# Power_Supplies.net
KiCad netlist of a schematic drawn in Altium Designer
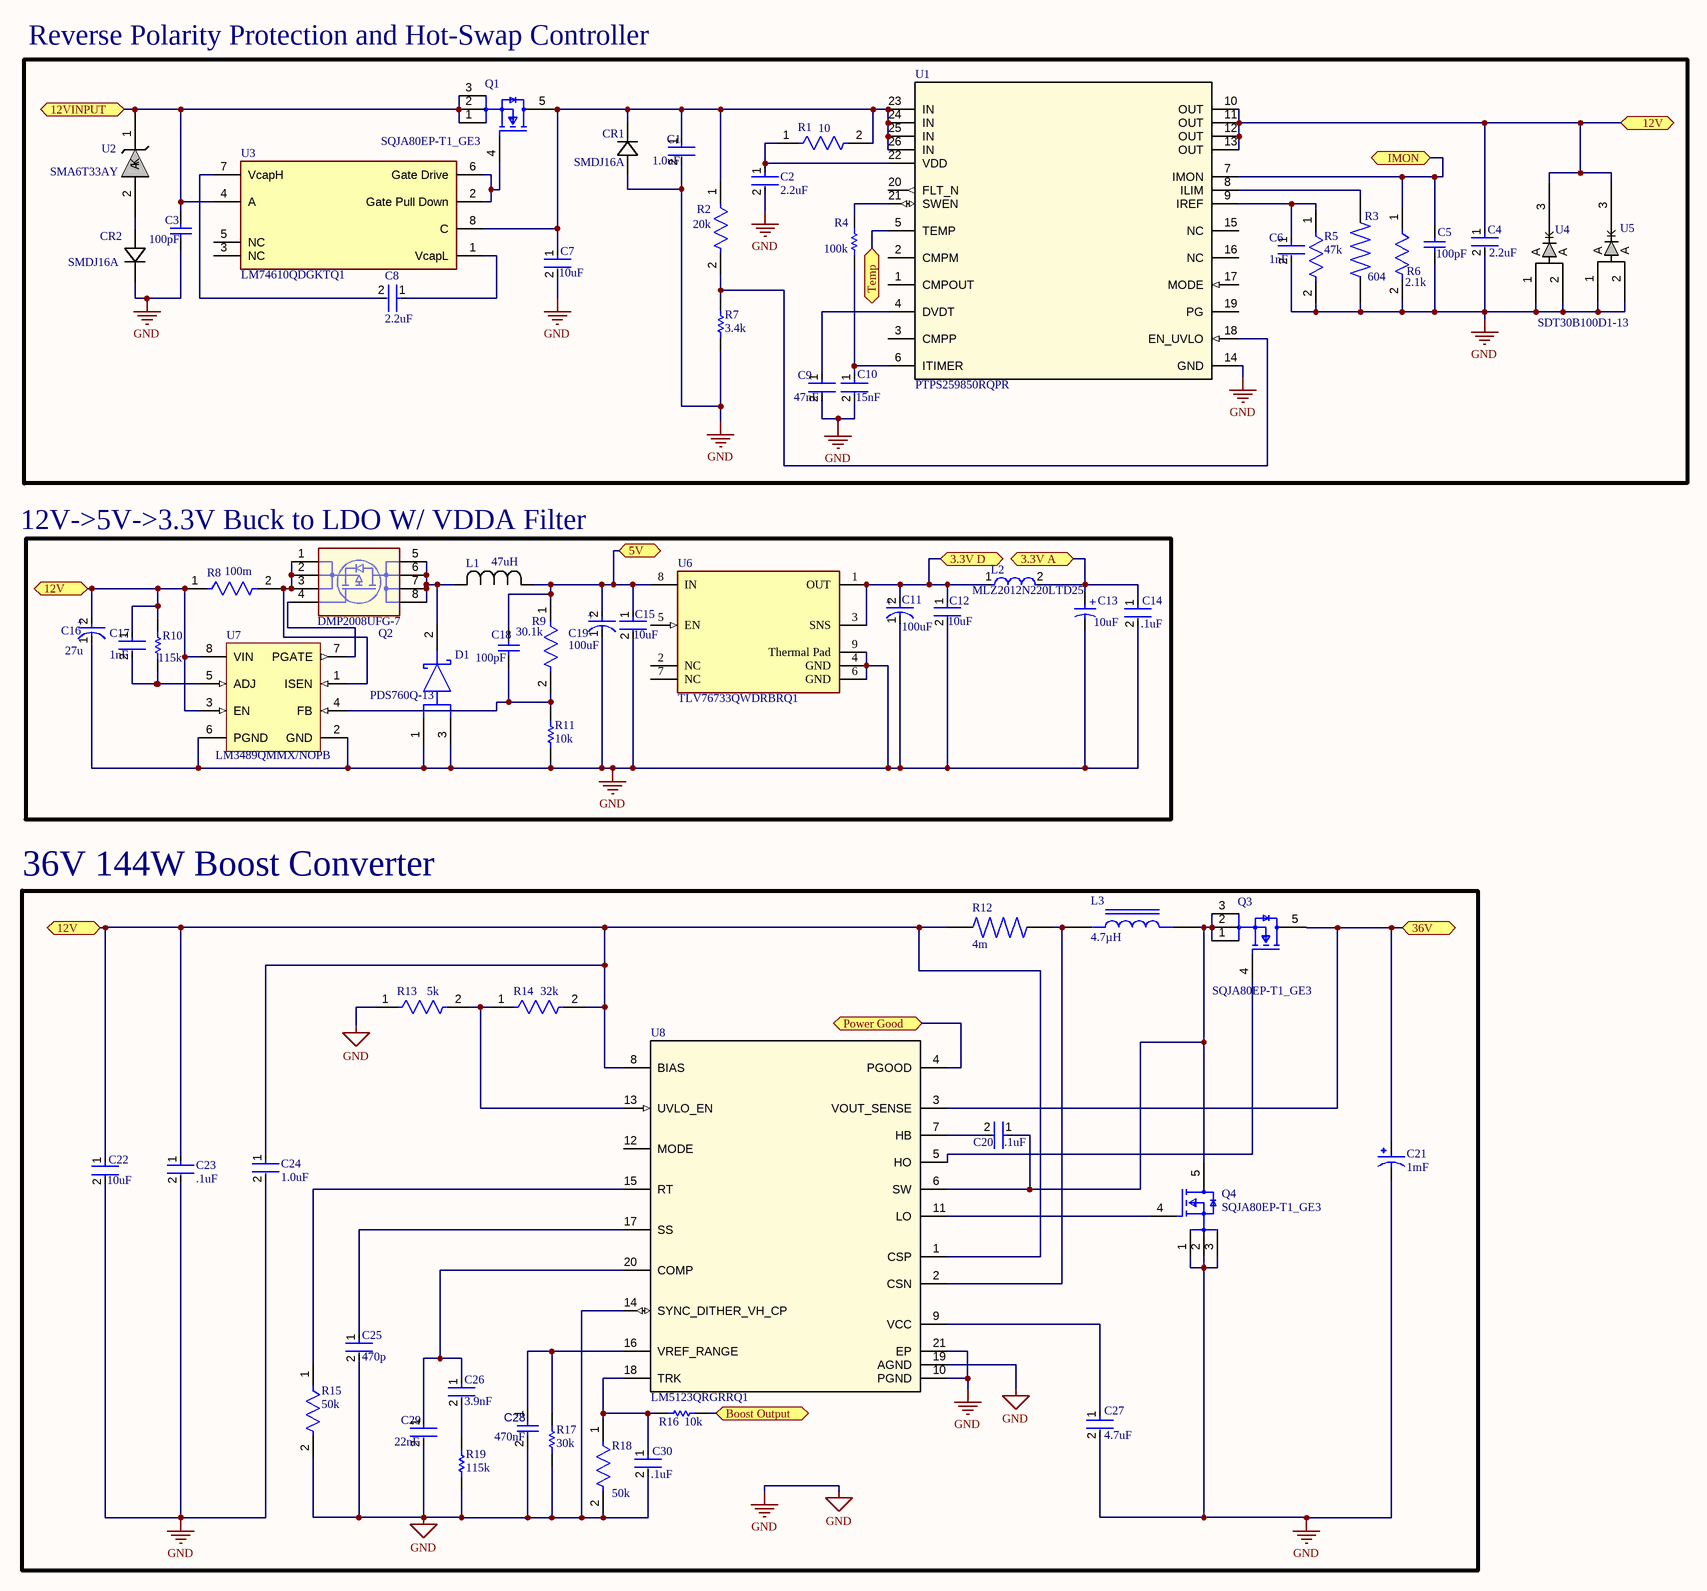
[diagram p0: Power_Supplies.SchDoc]

(export (version "E")
  (design (tool "Eeschema 10.0.6"))
  (components
    (comp (ref "C1")
      (value "1.0uF")
      (footprint "FP-GRM155-0_1-MFG")
      (description "Chip Multilayer Ceramic Capacitors for General Purpose, 0402, 1.0uF, X5R, 15%, 10%, 50V")
      (libsource (lib "Altium Content Vault") (part "11868f565c42a9108669ba33697ecf6"))
    )
    (comp (ref "C2")
      (value "2.2uF")
      (footprint "FP-GRM155-0_2-IPC_B")
      (description "Chip Multilayer Ceramic Capacitors for General Purpose, 0402, 2.2uF, X5R, 15%, 10%, 16V")
      (fields (field (name "TOLERANCE") "10%"))
      (libsource (lib "Altium Content Vault") (part "b4654b650e69147ec39a6b967a45e02"))
    )
    (comp (ref "C3")
      (value "100pF")
      (footprint "CAPC1005X55X25ML05T05")
      (description "Multilayer Ceramic Capacitor, 100 pF, 25 V, ± 10%, X7R, 0402 [1005 Metric]")
      (fields (field (name "PART NUMBER") "VJ0402Y101KXXPW1BC") (field (name "MANUFACTURER") "Vitramon"))
      (libsource (lib "Altium Content Vault") (part "CAP"))
    )
    (comp (ref "C4")
      (value "2.2uF")
      (footprint "FP-GRM155-0_2-IPC_B")
      (description "Chip Multilayer Ceramic Capacitors for General Purpose, 0402, 2.2uF, X5R, 15%, 10%, 16V")
      (fields (field (name "TOLERANCE") "10%"))
      (libsource (lib "Altium Content Vault") (part "b4654b650e69147ec39a6b967a45e02"))
    )
    (comp (ref "C5")
      (value "100pF")
      (footprint "CAPC1005X55X25ML05T05")
      (description "Multilayer Ceramic Capacitor, 100 pF, 25 V, ± 10%, X7R, 0402 [1005 Metric]")
      (fields (field (name "PART NUMBER") "VJ0402Y101KXXPW1BC") (field (name "MANUFACTURER") "Vitramon"))
      (libsource (lib "Altium Content Vault") (part "CAP"))
    )
    (comp (ref "C6")
      (value "1nF")
      (footprint "FP-C1005-050-0_05-IPC_B")
      (description "Multilayer Ceramic Capacitors 1nF ±5% 100V C0G SMD 0402")
      (fields (field (name "TOLERANCE") "5%"))
      (libsource (lib "Altium Content Vault") (part "b4654b650e69147ec39a6b967a45e02"))
    )
    (comp (ref "C7")
      (value "10uF")
      (footprint "FP-CL21-IPC_A")
      (description "CL21 Series 0805 10uF 25V ±10% Tolerance X5R Multilayer Ceramic Chip Capacitor")
      (fields (field (name "TOLERANCE") "10%"))
      (libsource (lib "Altium Content Vault") (part "b4654b650e69147ec39a6b967a45e02"))
    )
    (comp (ref "C8")
      (value "2.2uF")
      (footprint "FP-GRM155-0_2-IPC_B")
      (description "Chip Multilayer Ceramic Capacitors for General Purpose, 0402, 2.2uF, X5R, 15%, 10%, 16V")
      (fields (field (name "TOLERANCE") "10%"))
      (libsource (lib "Altium Content Vault") (part "b4654b650e69147ec39a6b967a45e02"))
    )
    (comp (ref "C9")
      (value "47nF")
      (footprint "FP-C1005-050-0_05-IPC_B")
      (description "Multilayer Ceramic Capacitors 47nF ±10% 35V X7R SMD 0402")
      (fields (field (name "TOLERANCE") "10%"))
      (libsource (lib "Altium Content Vault") (part "b4654b650e69147ec39a6b967a45e02"))
    )
    (comp (ref "C10")
      (value "15nF")
      (footprint "FP-GRT155-0_05-IPC_A")
      (description "Multi-Layer Ceramic Capacitor 15nF 50V X7R ±10% 0402 Paper T/R")
      (libsource (lib "Altium Content Vault") (part "02cd4be3c70576c341d710602a673aa"))
    )
    (comp (ref "C11")
      (value "100uF")
      (footprint "FP-FKF-MFG")
      (description "Radial Can - SMD ALUMINUM ELECTROLYTIC CAPACITOR FK 50V 100muF ±20% 0.315Dia 8.00mm")
      (fields (field (name "VOLTAGE") "50V") (field (name "TOLERANCE") "20%"))
      (libsource (lib "Altium Content Vault") (part "a00bbbee19879c290e62620ae7e47b1"))
    )
    (comp (ref "C12")
      (value "10uF")
      (footprint "FP-CL21-IPC_A")
      (description "CL21 Series 0805 10uF 25V ±10% Tolerance X5R Multilayer Ceramic Chip Capacitor")
      (fields (field (name "TOLERANCE") "10%"))
      (libsource (lib "Altium Content Vault") (part "b4654b650e69147ec39a6b967a45e02"))
    )
    (comp (ref "C13")
      (value "10uF")
      (footprint "WCAP-ASLI_D4H5.5")
      (description "865080340001 WCAP-ASLI Aluminum Electrolytic Capacitors")
      (fields (field (name "TOLERANCE") "20%"))
      (libsource (lib "Altium Content Vault") (part "Capacitor_Polarized"))
    )
    (comp (ref "C14")
      (value ".1uF")
      (footprint "FP-GRM155-0_05-MFG")
      (description "Chip Multilayer Ceramic Capacitors for General Purpose, 0402, 0.10uF, B, 10%, 10%, 50V")
      (fields (field (name "TOLERANCE") "10%"))
      (libsource (lib "Altium Content Vault") (part "02cd4be3c70576c341d710602a673aa"))
    )
    (comp (ref "C15")
      (value "10uF")
      (footprint "FP-CL21-IPC_A")
      (description "CL21 Series 0805 10uF 25V ±10% Tolerance X5R Multilayer Ceramic Chip Capacitor")
      (fields (field (name "TOLERANCE") "10%"))
      (libsource (lib "Altium Content Vault") (part "b4654b650e69147ec39a6b967a45e02"))
    )
    (comp (ref "C16")
      (value "27u")
      (footprint "FP-OS-CON-SMT-C6-MFG")
      (description "Conductive Polymer Aluminum Solid Capacitors (OS-CON) 27uF ±20% 20V")
      (fields (field (name "VOLTAGE") "20V") (field (name "TOLERANCE") "20%"))
      (libsource (lib "Altium Content Vault") (part "a00bbbee19879c290e62620ae7e47b1"))
    )
    (comp (ref "C17")
      (value "1nF")
      (footprint "FP-C1005-050-0_05-IPC_B")
      (description "Multilayer Ceramic Capacitors 1nF ±5% 100V C0G SMD 0402")
      (fields (field (name "TOLERANCE") "5%"))
      (libsource (lib "Altium Content Vault") (part "b4654b650e69147ec39a6b967a45e02"))
    )
    (comp (ref "C18")
      (value "100pF")
      (footprint "CAPC1005X55X25ML05T05")
      (fields (field (name "PART NUMBER") "VJ0402Y101KXXPW1BC") (field (name "MANUFACTURER") "Vitramon"))
      (libsource (lib "Altium Content Vault") (part "CAP"))
    )
    (comp (ref "C19")
      (value "100uF")
      (footprint "FP-FKF-MFG")
      (description "Radial Can - SMD ALUMINUM ELECTROLYTIC CAPACITOR FK 50V 100muF ±20% 0.315Dia 8.00mm")
      (fields (field (name "VOLTAGE") "50V") (field (name "TOLERANCE") "20%"))
      (libsource (lib "Altium Content Vault") (part "a00bbbee19879c290e62620ae7e47b1"))
    )
    (comp (ref "C20")
      (value ".1uF")
      (footprint "FP-GRM155-0_05-MFG")
      (description "Chip Multilayer Ceramic Capacitors for General Purpose, 0402, 0.10uF, B, 10%, 10%, 50V")
      (fields (field (name "TOLERANCE") "10%"))
      (libsource (lib "Altium Content Vault") (part "02cd4be3c70576c341d710602a673aa"))
    )
    (comp (ref "C21")
      (value "1mF")
      (footprint "CAP_EEEFK1H102AV")
      (description "1000ÂµF 50V Aluminum Electrolytic Capacitors Radial, Can - SMD 73mOhm @ 100kHz 5000 Hrs @ 105Â°C")
      (fields (field (name "MF") "Panasonic") (field (name "MP") "EEE-FK1H102AV"))
      (libsource (lib "Americas - California State Polytechnic University, Pomona - Bronco Motorsports") (part "EEEFK1H102AV"))
    )
    (comp (ref "C22")
      (value "10uF")
      (footprint "FP-CL21-IPC_A")
      (description "CL21 Series 0805 10uF 25V ±10% Tolerance X5R Multilayer Ceramic Chip Capacitor")
      (fields (field (name "TOLERANCE") "10%"))
      (libsource (lib "Altium Content Vault") (part "b4654b650e69147ec39a6b967a45e02"))
    )
    (comp (ref "C23")
      (value ".1uF")
      (footprint "FP-GRM155-0_05-MFG")
      (description "Chip Multilayer Ceramic Capacitors for General Purpose, 0402, 0.10uF, B, 10%, 10%, 50V")
      (fields (field (name "TOLERANCE") "10%"))
      (libsource (lib "Altium Content Vault") (part "02cd4be3c70576c341d710602a673aa"))
    )
    (comp (ref "C24")
      (value "1.0uF")
      (footprint "FP-GRM155-0_1-MFG")
      (description "Chip Multilayer Ceramic Capacitors for General Purpose, 0402, 1.0uF, X5R, 15%, 10%, 50V")
      (libsource (lib "Altium Content Vault") (part "11868f565c42a9108669ba33697ecf6"))
    )
    (comp (ref "C25")
      (value "470p")
      (footprint "FP-GCM155-0_1-IPC_A")
      (description "Ceramic Capacitor for Automotive 470nF ±20% 10VDC X7S 0402 Paper T/R")
      (libsource (lib "Altium Content Vault") (part "11868f565c42a9108669ba33697ecf6"))
    )
    (comp (ref "C26")
      (value "3.9nF")
      (footprint "FP-CC0402-MFG")
      (description "CAP CER 3900PF 50V X7R 0402")
      (fields
        (field (name "OCTOPART") "https://octopart.com/cc0402krx7r9bb392-yageo-9291741")
        (field (name "TOLERANCE") "0.1")
      )
      (libsource (lib "Altium Content Vault") (part "11868f565c42a9108669ba33697ecf6"))
    )
    (comp (ref "C27")
      (value "4.7uF")
      (footprint "FP-CL829-IPC_C")
      (description "Cap Ceramic 4.7uF 16V X5R ±20% SMD 0402 +85°C Paper T/R")
      (fields (field (name "TOLERANCE") "20%"))
      (libsource (lib "Altium Content Vault") (part "b4654b650e69147ec39a6b967a45e02"))
    )
    (comp (ref "C28")
      (value "470nF")
      (footprint "CAPC0402(1005)60_L")
      (description "Chip Capacitor, 470nF +/-40%, 10V, 0402, Thickness 0.6 mm")
      (fields (field (name "TOLERANCE") "20%") (field (name "Comment") "Capacitor 470nF +/-40% 10V 0402"))
      (libsource (lib "Americas - California State Polytechnic University, Pomona - Bronco Motorsports") (part "CAP-NP-2"))
    )
    (comp (ref "C29")
      (value "22nF")
      (footprint "FP-0402-L_1_0_0_05-W_0_5-IPC_B")
      (description "Multilayer Ceramic Capacitor 0.022uF 16V 10% 0402 Paper T/R")
      (libsource (lib "Altium Content Vault") (part "b4654b650e69147ec39a6b967a45e02"))
    )
    (comp (ref "C30")
      (value ".1uF")
      (footprint "FP-GRM155-0_05-MFG")
      (description "Chip Multilayer Ceramic Capacitors for General Purpose, 0402, 0.10uF, B, 10%, 10%, 50V")
      (fields (field (name "TOLERANCE") "10%"))
      (libsource (lib "Altium Content Vault") (part "02cd4be3c70576c341d710602a673aa"))
    )
    (comp (ref "CR1")
      (value "SMDJ16A")
      (footprint "SMDJSeries_LTF")
      (description "Description")
      (fields (field (name "COPYRIGHT") "Copyright (C) 2025 Ultra Librarian. All rights reserved."))
      (libsource (lib "Americas - California State Polytechnic University, Pomona - Bronco Motorsports") (part "SMDJ16A"))
    )
    (comp (ref "CR2")
      (value "SMDJ16A")
      (footprint "SMDJSeries_LTF")
      (description "Description")
      (fields (field (name "COPYRIGHT") "Copyright (C) 2025 Ultra Librarian. All rights reserved."))
      (libsource (lib "Americas - California State Polytechnic University, Pomona - Bronco Motorsports") (part "SMDJ16A"))
    )
    (comp (ref "D1")
      (value "PDS760Q-13")
      (footprint "FP-PowerDI5-MFG")
      (description "DIODE SCHOTTKY 60V 7A POWERDI5")
      (libsource (lib "Altium Content Vault") (part "72f53422dd85bf15edf9c11c54f6d52"))
    )
    (comp (ref "L1")
      (value "47uH")
      (footprint "IND_PA4343PM4343_FP2_PUL")
      (description "Description")
      (fields
        (field (name "MANUFACTURER_PART_NUMBER") "PM4343.473NLT")
        (field (name "COPYRIGHT") "Copyright (C) 2025 Ultra Librarian. All rights reserved.")
      )
      (libsource (lib "Americas - California State Polytechnic University, Pomona - Bronco Motorsports") (part "PM4343.473NLT"))
    )
    (comp (ref "L2")
      (value "MLZ2012N220LTD25")
      (footprint "FP-MLZ2012-1_25-IPC_A")
      (description "Shielded Multilayer Inductor 22uH ±20% 300mA 871mΩ AEC-Q200 SMD 0805")
      (fields (field (name "TOLERANCE") "20%"))
      (libsource (lib "Altium Content Vault") (part "725321dda6339637d4d059423bc1c3c"))
    )
    (comp (ref "L3")
      (value "4.7µH")
      (footprint "IND_PQ2614BLA-4R7K")
      (fields (field (name "MP") "PQ2614BLA-4R7K") (field (name "MF") "{'manufacturer': u'Bourns Inc.'}"))
      (libsource (lib "Americas - California State Polytechnic University, Pomona - Bronco Motorsports") (part "PQ2614BLA-4R7K"))
    )
    (comp (ref "Q1")
      (value "SQJA80EP-T1_GE3")
      (footprint "FP-S19-0643-SINGLE-MFG")
      (description "MOSFET N-CH 80V 60A POWERPAKSO-8")
      (libsource (lib "Altium Content Vault") (part "ce91e87c6664544d97c68d339304545"))
    )
    (comp (ref "Q2")
      (value "DMP2008UFG-7")
      (footprint "DMP2008UFG-7_DIO")
      (description "Description")
      (fields (field (name "COPYRIGHT") "Copyright (C) 2025 Ultra Librarian. All rights reserved."))
      (libsource (lib "Americas - California State Polytechnic University, Pomona - Bronco Motorsports") (part "DMP2008UFG-7"))
    )
    (comp (ref "Q3")
      (value "SQJA80EP-T1_GE3")
      (footprint "FP-S19-0643-SINGLE-MFG")
      (description "MOSFET N-CH 80V 60A POWERPAKSO-8")
      (libsource (lib "Altium Content Vault") (part "ce91e87c6664544d97c68d339304545"))
    )
    (comp (ref "Q4")
      (value "SQJA80EP-T1_GE3")
      (footprint "FP-S19-0643-SINGLE-MFG")
      (description "MOSFET N-CH 80V 60A POWERPAKSO-8")
      (libsource (lib "Altium Content Vault") (part "ce91e87c6664544d97c68d339304545"))
    )
    (comp (ref "R1")
      (value "10")
      (footprint "FP-RP73P-1E-MFG")
      (description "RP73P 0402 10Ω 0.1W 25ppm/°C 0.10% 50V")
      (fields (field (name "TOLERANCE") "0.10%") (field (name "MANUFACTURER") "TE Connectivity"))
      (libsource (lib "Altium Content Vault") (part "1029c3af85768c4190bb7ad29bc67b5"))
    )
    (comp (ref "R2")
      (value "20k")
      (footprint "FP-AC0402-IPC_A")
      (description "RES 20kΩ ±1% 0.125W 0402")
      (libsource (lib "Altium Content Vault") (part "1029c3af85768c4190bb7ad29bc67b5"))
    )
    (comp (ref "R3")
      (value "604")
      (footprint "RES_ERA3AEB6040V")
      (fields
        (field (name "MF") "{'manufacturer': u'Panasonic Electronic Components'}")
        (field (name "MP") "ERA3AEB6040V")
      )
      (libsource (lib "Americas - California State Polytechnic University, Pomona - Bronco Motorsports") (part "ERA3AEB6040V"))
    )
    (comp (ref "R4")
      (value "100k")
      (footprint "RESC1005X40X25ML05T10")
      (description "Res Thick Film 0402 100K Ohm 1% 0.063W(1/16W) ±100ppm/C Pad SMD T/R")
      (fields (field (name "MANUFACTURER") "Yageo") (field (name "PART NUMBER") "RC0402FR-13100KL"))
      (libsource (lib "Altium Content Vault") (part "RES"))
    )
    (comp (ref "R5")
      (value "47k")
      (footprint "FP-RT0603-MFG")
      (description "RES SMD 47K OHM 0.1% 1/10W 0603")
      (fields (field (name "MANUFACTURER") "Yageo") (field (name "TOLERANCE") "0.001"))
      (libsource (lib "Altium Content Vault") (part "1029c3af85768c4190bb7ad29bc67b5"))
    )
    (comp (ref "R6")
      (value "2.1k")
      (footprint "FP-RG1608-IPC_C")
      (description "Automotive Metal Thin Film Chip Resistor, 0603, 2.1kΩ, 0.1%, 25ppm/°C, 0.1W, 100V")
      (fields (field (name "TOLERANCE") "0.1%"))
      (libsource (lib "Altium Content Vault") (part "1029c3af85768c4190bb7ad29bc67b5"))
    )
    (comp (ref "R7")
      (value "3.4k")
      (footprint "RESC2013X60X30ML20T20")
      (fields (field (name "PART NUMBER") "RK73H2ATTD3401F") (field (name "MANUFACTURER") "KOA Speer"))
      (libsource (lib "Altium Content Vault") (part "RES"))
    )
    (comp (ref "R8")
      (value "100m")
      (footprint "FP-CSRN2512-IPC_B")
      (description "Res Thick Film 2512 0.1Ω 1% 2W ±200ppm/°C Molded SMD Plastic T/R")
      (fields (field (name "TOLERANCE") "1%"))
      (libsource (lib "Altium Content Vault") (part "1029c3af85768c4190bb7ad29bc67b5"))
    )
    (comp (ref "R9")
      (value "30.1k")
      (footprint "FP-RK73H1E-MFG")
      (description "30.1kΩ ±1% 0.1W Chip Resistor 0402 Thick Film AEC-Q200 Qualified")
      (fields (field (name "TOLERANCE") "1%"))
      (libsource (lib "Altium Content Vault") (part "1029c3af85768c4190bb7ad29bc67b5"))
    )
    (comp (ref "R10")
      (value "115k")
      (footprint "RESC1005X40X25ML05T10")
      (description "Res Thick Film 0402 115K Ohm 1% 0.063W(1/16W) ±100ppm/C Pad SMD T/R")
      (fields (field (name "PART NUMBER") "RC0402FR-07115KL") (field (name "MANUFACTURER") "Yageo / Phycomp"))
      (libsource (lib "Altium Content Vault") (part "RES"))
    )
    (comp (ref "R11")
      (value "10k")
      (footprint "RESC1005X40X25ML05T10")
      (fields (field (name "PART NUMBER") "CRCW040210K0FKEDHP") (field (name "MANUFACTURER") "Vishay Dale"))
      (libsource (lib "Altium Content Vault") (part "RES"))
    )
    (comp (ref "R12")
      (value "4m")
      (footprint "RESC6331X87N")
      (description "4 mOhms Â±1% 3W Chip Resistor 2512 (6432 Metric) Automotive AEC-Q200, Current Sense Metal Element")
      (fields (field (name "MP") "TLR3APDTE4L00F75") (field (name "MF") "KOA Speer"))
      (libsource (lib "Americas - California State Polytechnic University, Pomona - Bronco Motorsports") (part "TLR3APDTE4L00F75"))
    )
    (comp (ref "R13")
      (value "5k")
      (footprint "FP-RC0402-MFG")
      (description "RES SMD 5K OHM 1% 1/16W 0402")
      (fields (field (name "MANUFACTURER") "Yageo") (field (name "TOLERANCE") "1%"))
      (libsource (lib "Altium Content Vault") (part "1029c3af85768c4190bb7ad29bc67b5"))
    )
    (comp (ref "R14")
      (value "32k")
      (footprint "FP-RN73R1E-IPC_C")
      (description "32kΩ ±0.1% 0.063W, 1/16W Chip Resistor 0402 (1005 Metric) Moisture Resistant Thin Film")
      (libsource (lib "Altium Content Vault") (part "1029c3af85768c4190bb7ad29bc67b5"))
    )
    (comp (ref "R15")
      (value "50k")
      (footprint "FP-CRCW0402-e3-IPC_A")
      (description "RES Thick Film, 50kΩ, 1%, 0.063W, 100ppm/°C, 0402")
      (fields (field (name "TOLERANCE") "1%"))
      (libsource (lib "Altium Content Vault") (part "1029c3af85768c4190bb7ad29bc67b5"))
    )
    (comp (ref "R16")
      (value "10k")
      (footprint "RESC1005X40X25ML05T10")
      (fields (field (name "PART NUMBER") "CRCW040210K0FKEDHP") (field (name "MANUFACTURER") "Vishay Dale"))
      (libsource (lib "Altium Content Vault") (part "RES"))
    )
    (comp (ref "R17")
      (value "30k")
      (footprint "RESC2013X60X35LL10T20")
      (fields (field (name "PART NUMBER") "RC0805JR-0730KL") (field (name "MANUFACTURER") "Yageo"))
      (libsource (lib "Altium Content Vault") (part "RES"))
    )
    (comp (ref "R18")
      (value "50k")
      (footprint "FP-CRCW0402-e3-IPC_A")
      (description "RES Thick Film, 50kΩ, 1%, 0.063W, 100ppm/°C, 0402")
      (fields (field (name "TOLERANCE") "1%"))
      (libsource (lib "Altium Content Vault") (part "1029c3af85768c4190bb7ad29bc67b5"))
    )
    (comp (ref "R19")
      (value "115k")
      (footprint "RESC1005X40X25ML05T10")
      (fields (field (name "PART NUMBER") "RC0402FR-07115KL") (field (name "MANUFACTURER") "Yageo / Phycomp"))
      (libsource (lib "Altium Content Vault") (part "RES"))
    )
    (comp (ref "U1")
      (value "PTPS259850RQPR")
      (footprint "RQP0026A-MFG")
      (fields (field (name "COPYRIGHT") "Copyright (C) 2025 Ultra Librarian. All rights reserved."))
      (libsource (lib "Americas - California State Polytechnic University, Pomona - Bronco Motorsports") (part "PTPS259850RQPR"))
    )
    (comp (ref "U2")
      (value "SMA6T33AY")
      (footprint "SMA_UNI_STM")
      (description "Automotive 600 W, 28.2 V TVS in SMA")
      (fields (field (name "COPYRIGHT") "Copyright (C) 2025 Ultra Librarian. All rights reserved."))
      (libsource (lib "Americas - California State Polytechnic University, Pomona - Bronco Motorsports") (part "SMA6T33AY"))
    )
    (comp (ref "U3")
      (value "LM74610QDGKTQ1")
      (footprint "FP-DGK0008A-MFG")
      (description "IC SMART DIODE CTLR 8VSSOP")
      (fields
        (field (name "MANUFACTURER") "Texas Instruments")
        (field (name "OCTOPART") "https://octopart.com/lm74610qdgktq1-texas+instruments-61765970")
      )
      (libsource (lib "Altium Content Vault") (part "c7658b1ea207364c60caa1c767b42c9"))
    )
    (comp (ref "U4")
      (value "SDT30B100D1-13")
      (footprint "TO252_DIO")
      (description "Description")
      (fields (field (name "COPYRIGHT") "Copyright (C) 2025 Ultra Librarian. All rights reserved."))
      (libsource (lib "Americas - California State Polytechnic University, Pomona - Bronco Motorsports") (part "SDT30B100D1-13"))
    )
    (comp (ref "U5")
      (value "SDT30B100D1-13")
      (footprint "TO252_DIO")
      (description "Description")
      (fields (field (name "COPYRIGHT") "Copyright (C) 2025 Ultra Librarian. All rights reserved."))
      (libsource (lib "Americas - California State Polytechnic University, Pomona - Bronco Motorsports") (part "SDT30B100D1-13"))
    )
    (comp (ref "U6")
      (value "TLV76733QWDRBRQ1")
      (footprint "FP-DRB0008J-IPC_C")
      (description "IC REG LIN 3.3V 1A 8SON Linear Voltage Regulator IC Positive Fixed 1 Output 1A 8-SON (3x3)")
      (libsource (lib "Americas - California State Polytechnic University, Pomona - Bronco Motorsports") (part "986f8d1759350ee61d4b04c225c65ee"))
    )
    (comp (ref "U7")
      (value "LM3489QMMX/NOPB")
      (footprint "DGK0008A_M")
      (description "Hysteretic PFET Buck Controller with Enable Pin, 8-pin MSOP, Pb-Free")
      (fields (field (name "MANUFACTURER") "Texas Instruments"))
      (libsource (lib "Altium Content Vault") (part "PM-REG-LM3489-8"))
    )
    (comp (ref "U8")
      (value "LM5123QRGRRQ1")
      (footprint "RGR0020C-IPC_A")
      (description "2.2MHz wide VIN low IQ synchronous boost controller 20-VQFN -40 to 150")
      (fields (field (name "COPYRIGHT") "Copyright (C) 2025 Ultra Librarian. All rights reserved."))
      (libsource (lib "Americas - California State Polytechnic University, Pomona - Bronco Motorsports") (part "LM5123QRGRRQ1"))
    )
  )
  (nets
    (net (code "1") (name "/3.3V A") (class "Default")
      (node (ref "C13") (pin "1") (pinfunction "P_1") (pintype "passive"))
      (node (ref "C14") (pin "1") (pinfunction "1_1") (pintype "passive"))
      (node (ref "L2") (pin "2") (pinfunction "2_2") (pintype "passive"))
    )
    (net (code "2") (name "/3.3V D") (class "Default")
      (node (ref "C11") (pin "2") (pinfunction "A_2") (pintype "passive"))
      (node (ref "C12") (pin "1") (pinfunction "1_1") (pintype "passive"))
      (node (ref "L2") (pin "1") (pinfunction "1_1") (pintype "passive"))
      (node (ref "U6") (pin "1") (pinfunction "OUT_1") (pintype "power_in"))
      (node (ref "U6") (pin "3") (pinfunction "SNS_3") (pintype "passive"))
    )
    (net (code "3") (name "/5V") (class "Default")
      (node (ref "C15") (pin "1") (pinfunction "1_1") (pintype "passive"))
      (node (ref "C18") (pin "1") (pinfunction "1_1") (pintype "passive"))
      (node (ref "C19") (pin "2") (pinfunction "A_2") (pintype "passive"))
      (node (ref "L1") (pin "1") (pinfunction "1_1") (pintype "passive"))
      (node (ref "R9") (pin "1") (pinfunction "1_1") (pintype "passive"))
      (node (ref "U6") (pin "8") (pinfunction "IN_8") (pintype "power_in"))
    )
    (net (code "4") (name "/12V") (class "Default")
      (node (ref "C16") (pin "2") (pinfunction "A_2") (pintype "passive"))
      (node (ref "C17") (pin "1") (pinfunction "1_1") (pintype "passive"))
      (node (ref "C22") (pin "1") (pinfunction "1_1") (pintype "passive"))
      (node (ref "C23") (pin "1") (pinfunction "1_1") (pintype "passive"))
      (node (ref "C24") (pin "1") (pinfunction "1_1") (pintype "passive"))
      (node (ref "C4") (pin "1") (pinfunction "1_1") (pintype "passive"))
      (node (ref "R10") (pin "1") (pinfunction "1_1") (pintype "passive"))
      (node (ref "R12") (pin "1") (pinfunction "1_1") (pintype "passive"))
      (node (ref "R14") (pin "2") (pinfunction "2_2") (pintype "passive"))
      (node (ref "R8") (pin "1") (pinfunction "1_1") (pintype "passive"))
      (node (ref "U1") (pin "10") (pinfunction "OUT_10") (pintype "power_in"))
      (node (ref "U1") (pin "11") (pinfunction "OUT_11") (pintype "power_in"))
      (node (ref "U1") (pin "12") (pinfunction "OUT_12") (pintype "power_in"))
      (node (ref "U1") (pin "13") (pinfunction "OUT_13") (pintype "power_in"))
      (node (ref "U4") (pin "3") (pinfunction "K_3") (pintype "passive"))
      (node (ref "U5") (pin "3") (pinfunction "K_3") (pintype "passive"))
      (node (ref "U7") (pin "3") (pinfunction "EN_3") (pintype "input"))
      (node (ref "U7") (pin "8") (pinfunction "VIN_8") (pintype "power_in"))
      (node (ref "U8") (pin "1") (pinfunction "CSP_1") (pintype "tri_state"))
      (node (ref "U8") (pin "8") (pinfunction "BIAS_8") (pintype "power_in"))
    )
    (net (code "5") (name "/12VINPUT") (class "Default")
      (node (ref "C3") (pin "1") (pinfunction "1_1") (pintype "passive"))
      (node (ref "Q1") (pin "1") (pinfunction "S_1") (pintype "passive"))
      (node (ref "Q1") (pin "2") (pinfunction "S_2") (pintype "passive"))
      (node (ref "Q1") (pin "3") (pinfunction "S_3") (pintype "passive"))
      (node (ref "U2") (pin "1") (pinfunction "K_1") (pintype "passive"))
      (node (ref "U3") (pin "4") (pinfunction "A_4") (pintype "passive"))
    )
    (net (code "6") (name "/36V") (class "Default")
      (node (ref "C21") (pin "1") (pinfunction "1_1") (pintype "passive"))
      (node (ref "Q3") (pin "5") (pinfunction "D_5") (pintype "passive"))
      (node (ref "U8") (pin "3") (pinfunction "VOUT_SENSE_3") (pintype "passive"))
    )
    (net (code "7") (name "/Boost Output") (class "Default")
      (node (ref "R16") (pin "1") (pinfunction "1_1") (pintype "passive"))
    )
    (net (code "8") (name "/IMON") (class "Default")
      (node (ref "C5") (pin "1") (pinfunction "1_1") (pintype "passive"))
      (node (ref "R6") (pin "1") (pinfunction "1_1") (pintype "passive"))
      (node (ref "U1") (pin "7") (pinfunction "IMON_7") (pintype "passive"))
    )
    (net (code "9") (name "/Power Good") (class "Default")
      (node (ref "U8") (pin "4") (pinfunction "PGOOD_4") (pintype "open_collector"))
    )
    (net (code "10") (name "/Temp") (class "Default")
      (node (ref "U1") (pin "5") (pinfunction "TEMP_5") (pintype "passive"))
    )
    (net (code "11") (name "GND") (class "Default")
      (node (ref "C1") (pin "2") (pinfunction "2_2") (pintype "passive"))
      (node (ref "C10") (pin "2") (pinfunction "2_2") (pintype "passive"))
      (node (ref "C11") (pin "1") (pinfunction "C_1") (pintype "passive"))
      (node (ref "C12") (pin "2") (pinfunction "2_2") (pintype "passive"))
      (node (ref "C13") (pin "2") (pinfunction "N_2") (pintype "passive"))
      (node (ref "C14") (pin "2") (pinfunction "2_2") (pintype "passive"))
      (node (ref "C15") (pin "2") (pinfunction "2_2") (pintype "passive"))
      (node (ref "C16") (pin "1") (pinfunction "C_1") (pintype "passive"))
      (node (ref "C19") (pin "1") (pinfunction "C_1") (pintype "passive"))
      (node (ref "C2") (pin "2") (pinfunction "2_2") (pintype "passive"))
      (node (ref "C21") (pin "2") (pinfunction "2_2") (pintype "passive"))
      (node (ref "C22") (pin "2") (pinfunction "2_2") (pintype "passive"))
      (node (ref "C23") (pin "2") (pinfunction "2_2") (pintype "passive"))
      (node (ref "C24") (pin "2") (pinfunction "2_2") (pintype "passive"))
      (node (ref "C25") (pin "2") (pinfunction "2_2") (pintype "passive"))
      (node (ref "C27") (pin "2") (pinfunction "2_2") (pintype "passive"))
      (node (ref "C28") (pin "2") (pinfunction "2_2") (pintype "passive"))
      (node (ref "C29") (pin "2") (pinfunction "2_2") (pintype "passive"))
      (node (ref "C3") (pin "2") (pinfunction "2_2") (pintype "passive"))
      (node (ref "C30") (pin "2") (pinfunction "2_2") (pintype "passive"))
      (node (ref "C4") (pin "2") (pinfunction "2_2") (pintype "passive"))
      (node (ref "C5") (pin "2") (pinfunction "2_2") (pintype "passive"))
      (node (ref "C6") (pin "2") (pinfunction "2_2") (pintype "passive"))
      (node (ref "C7") (pin "2") (pinfunction "2_2") (pintype "passive"))
      (node (ref "C9") (pin "2") (pinfunction "2_2") (pintype "passive"))
      (node (ref "CR1") (pin "2") (pinfunction "2_2") (pintype "passive"))
      (node (ref "CR2") (pin "1") (pinfunction "1_1") (pintype "passive"))
      (node (ref "D1") (pin "1") (pinfunction "A_1") (pintype "passive"))
      (node (ref "D1") (pin "3") (pinfunction "A_3") (pintype "passive"))
      (node (ref "Q4") (pin "1") (pinfunction "S_1") (pintype "passive"))
      (node (ref "Q4") (pin "2") (pinfunction "S_2") (pintype "passive"))
      (node (ref "Q4") (pin "3") (pinfunction "S_3") (pintype "passive"))
      (node (ref "R11") (pin "2") (pinfunction "2_2") (pintype "passive"))
      (node (ref "R13") (pin "1") (pinfunction "1_1") (pintype "passive"))
      (node (ref "R15") (pin "2") (pinfunction "2_2") (pintype "passive"))
      (node (ref "R17") (pin "2") (pinfunction "2_2") (pintype "passive"))
      (node (ref "R18") (pin "2") (pinfunction "2_2") (pintype "passive"))
      (node (ref "R19") (pin "2") (pinfunction "2_2") (pintype "passive"))
      (node (ref "R3") (pin "2") (pinfunction "2_2") (pintype "passive"))
      (node (ref "R5") (pin "2") (pinfunction "2_2") (pintype "passive"))
      (node (ref "R6") (pin "2") (pinfunction "2_2") (pintype "passive"))
      (node (ref "R7") (pin "2") (pinfunction "2_2") (pintype "passive"))
      (node (ref "U1") (pin "14") (pinfunction "GND_14") (pintype "power_in"))
      (node (ref "U4") (pin "1") (pinfunction "A_1") (pintype "passive"))
      (node (ref "U4") (pin "2") (pinfunction "A_2") (pintype "passive"))
      (node (ref "U5") (pin "1") (pinfunction "A_1") (pintype "passive"))
      (node (ref "U5") (pin "2") (pinfunction "A_2") (pintype "passive"))
      (node (ref "U6") (pin "4") (pinfunction "GND_4") (pintype "power_in"))
      (node (ref "U6") (pin "6") (pinfunction "GND_6") (pintype "power_in"))
      (node (ref "U6") (pin "9") (pinfunction "Thermal_Pad_9") (pintype "passive"))
      (node (ref "U7") (pin "2") (pinfunction "GND_2") (pintype "power_in"))
      (node (ref "U7") (pin "6") (pinfunction "PGND_6") (pintype "power_in"))
      (node (ref "U8") (pin "10") (pinfunction "PGND_10") (pintype "power_in"))
      (node (ref "U8") (pin "14") (pinfunction "SYNC_DITHER_VH_CP_14") (pintype "bidirectional"))
      (node (ref "U8") (pin "19") (pinfunction "AGND_19") (pintype "power_in"))
      (node (ref "U8") (pin "21") (pinfunction "EP_21") (pintype "passive"))
    )
    (net (code "12") (name "Net-(C26-Pad2)") (class "Default")
      (node (ref "C26") (pin "2") (pinfunction "2_2") (pintype "passive"))
      (node (ref "R19") (pin "1") (pinfunction "1_1") (pintype "passive"))
    )
    (net (code "13") (name "Net-(D1-C)") (class "Default")
      (node (ref "D1") (pin "2") (pinfunction "C_2") (pintype "passive"))
      (node (ref "L1") (pin "2") (pinfunction "2_2") (pintype "passive"))
      (node (ref "Q2") (pin "5") (pinfunction "D_5") (pintype "passive"))
      (node (ref "Q2") (pin "6") (pinfunction "D_6") (pintype "passive"))
      (node (ref "Q2") (pin "7") (pinfunction "D_7") (pintype "passive"))
      (node (ref "Q2") (pin "8") (pinfunction "D_8") (pintype "passive"))
    )
    (net (code "14") (name "Net-(Q1-D)") (class "Default")
      (node (ref "C1") (pin "1") (pinfunction "1_1") (pintype "passive"))
      (node (ref "C7") (pin "1") (pinfunction "1_1") (pintype "passive"))
      (node (ref "CR1") (pin "1") (pinfunction "1_1") (pintype "passive"))
      (node (ref "Q1") (pin "5") (pinfunction "D_5") (pintype "passive"))
      (node (ref "R1") (pin "2") (pinfunction "2_2") (pintype "passive"))
      (node (ref "R2") (pin "1") (pinfunction "1_1") (pintype "passive"))
      (node (ref "U1") (pin "23") (pinfunction "IN_23") (pintype "power_in"))
      (node (ref "U1") (pin "24") (pinfunction "IN_24") (pintype "power_in"))
      (node (ref "U1") (pin "25") (pinfunction "IN_25") (pintype "power_in"))
      (node (ref "U1") (pin "26") (pinfunction "IN_26") (pintype "power_in"))
      (node (ref "U3") (pin "8") (pinfunction "C_8") (pintype "passive"))
    )
    (net (code "15") (name "Net-(Q1-G)") (class "Default")
      (node (ref "Q1") (pin "4") (pinfunction "G_4") (pintype "passive"))
      (node (ref "U3") (pin "2") (pinfunction "Gate_Pull_Down_2") (pintype "passive"))
      (node (ref "U3") (pin "6") (pinfunction "Gate_Drive_6") (pintype "passive"))
    )
    (net (code "16") (name "Net-(Q2-G)") (class "Default")
      (node (ref "Q2") (pin "4") (pinfunction "G_4") (pintype "passive"))
      (node (ref "U7") (pin "7") (pinfunction "PGATE_7") (pintype "output"))
    )
    (net (code "17") (name "Net-(Q3-G)") (class "Default")
      (node (ref "Q3") (pin "4") (pinfunction "G_4") (pintype "passive"))
      (node (ref "U8") (pin "5") (pinfunction "HO_5") (pintype "passive"))
    )
    (net (code "18") (name "Net-(Q4-D)") (class "Default")
      (node (ref "C20") (pin "1") (pinfunction "1_1") (pintype "passive"))
      (node (ref "L3") (pin "2") (pinfunction "2_2") (pintype "passive"))
      (node (ref "Q3") (pin "1") (pinfunction "S_1") (pintype "passive"))
      (node (ref "Q3") (pin "2") (pinfunction "S_2") (pintype "passive"))
      (node (ref "Q3") (pin "3") (pinfunction "S_3") (pintype "passive"))
      (node (ref "Q4") (pin "5") (pinfunction "D_5") (pintype "passive"))
      (node (ref "U8") (pin "6") (pinfunction "SW_6") (pintype "passive"))
    )
    (net (code "19") (name "Net-(Q4-G)") (class "Default")
      (node (ref "Q4") (pin "4") (pinfunction "G_4") (pintype "passive"))
      (node (ref "U8") (pin "11") (pinfunction "LO_11") (pintype "passive"))
    )
    (net (code "20") (name "Net-(U1-DVDT)") (class "Default")
      (node (ref "C9") (pin "1") (pinfunction "1_1") (pintype "passive"))
      (node (ref "U1") (pin "4") (pinfunction "DVDT_4") (pintype "passive"))
    )
    (net (code "21") (name "Net-(U1-EN_UVLO)") (class "Default")
      (node (ref "R2") (pin "2") (pinfunction "2_2") (pintype "passive"))
      (node (ref "R7") (pin "1") (pinfunction "1_1") (pintype "passive"))
      (node (ref "U1") (pin "18") (pinfunction "EN_UVLO_18") (pintype "input"))
    )
    (net (code "22") (name "Net-(U1-ILIM)") (class "Default")
      (node (ref "R3") (pin "1") (pinfunction "1_1") (pintype "passive"))
      (node (ref "U1") (pin "8") (pinfunction "ILIM_8") (pintype "passive"))
    )
    (net (code "23") (name "Net-(U1-IREF)") (class "Default")
      (node (ref "C6") (pin "1") (pinfunction "1_1") (pintype "passive"))
      (node (ref "R5") (pin "1") (pinfunction "1_1") (pintype "passive"))
      (node (ref "U1") (pin "9") (pinfunction "IREF_9") (pintype "passive"))
    )
    (net (code "24") (name "Net-(U1-ITIMER)") (class "Default")
      (node (ref "C10") (pin "1") (pinfunction "1_1") (pintype "passive"))
      (node (ref "R4") (pin "2") (pinfunction "2_2") (pintype "passive"))
      (node (ref "U1") (pin "6") (pinfunction "ITIMER_6") (pintype "passive"))
    )
    (net (code "25") (name "Net-(U1-SWEN)") (class "Default")
      (node (ref "R4") (pin "1") (pinfunction "1_1") (pintype "passive"))
      (node (ref "U1") (pin "21") (pinfunction "SWEN_21") (pintype "bidirectional"))
    )
    (net (code "26") (name "Net-(U1-VDD)") (class "Default")
      (node (ref "C2") (pin "1") (pinfunction "1_1") (pintype "passive"))
      (node (ref "R1") (pin "1") (pinfunction "1_1") (pintype "passive"))
      (node (ref "U1") (pin "22") (pinfunction "VDD_22") (pintype "power_in"))
    )
    (net (code "27") (name "Net-(U2-A)") (class "Default")
      (node (ref "CR2") (pin "2") (pinfunction "2_2") (pintype "passive"))
      (node (ref "U2") (pin "2") (pinfunction "A_2") (pintype "passive"))
    )
    (net (code "28") (name "Net-(U3-VcapH)") (class "Default")
      (node (ref "C8") (pin "2") (pinfunction "2_2") (pintype "passive"))
      (node (ref "U3") (pin "7") (pinfunction "VcapH_7") (pintype "power_in"))
    )
    (net (code "29") (name "Net-(U3-VcapL)") (class "Default")
      (node (ref "C8") (pin "1") (pinfunction "1_1") (pintype "passive"))
      (node (ref "U3") (pin "1") (pinfunction "VcapL_1") (pintype "power_in"))
    )
    (net (code "30") (name "Net-(U7-ADJ)") (class "Default")
      (node (ref "C17") (pin "2") (pinfunction "2_2") (pintype "passive"))
      (node (ref "R10") (pin "2") (pinfunction "2_2") (pintype "passive"))
      (node (ref "U7") (pin "5") (pinfunction "ADJ_5") (pintype "input"))
    )
    (net (code "31") (name "Net-(U7-FB)") (class "Default")
      (node (ref "C18") (pin "2") (pinfunction "2_2") (pintype "passive"))
      (node (ref "R11") (pin "1") (pinfunction "1_1") (pintype "passive"))
      (node (ref "R9") (pin "2") (pinfunction "2_2") (pintype "passive"))
      (node (ref "U7") (pin "4") (pinfunction "FB_4") (pintype "input"))
    )
    (net (code "32") (name "Net-(U7-ISEN)") (class "Default")
      (node (ref "Q2") (pin "1") (pinfunction "S_1") (pintype "passive"))
      (node (ref "Q2") (pin "2") (pinfunction "S_2") (pintype "passive"))
      (node (ref "Q2") (pin "3") (pinfunction "S_3") (pintype "passive"))
      (node (ref "R8") (pin "2") (pinfunction "2_2") (pintype "passive"))
      (node (ref "U7") (pin "1") (pinfunction "ISEN_1") (pintype "input"))
    )
    (net (code "33") (name "Net-(U8-COMP)") (class "Default")
      (node (ref "C26") (pin "1") (pinfunction "1_1") (pintype "passive"))
      (node (ref "C29") (pin "1") (pinfunction "1_1") (pintype "passive"))
      (node (ref "U8") (pin "20") (pinfunction "COMP_20") (pintype "passive"))
    )
    (net (code "34") (name "Net-(U8-CSN)") (class "Default")
      (node (ref "L3") (pin "1") (pinfunction "1_1") (pintype "passive"))
      (node (ref "R12") (pin "2") (pinfunction "2_2") (pintype "passive"))
      (node (ref "U8") (pin "2") (pinfunction "CSN_2") (pintype "tri_state"))
    )
    (net (code "35") (name "Net-(U8-HB)") (class "Default")
      (node (ref "C20") (pin "2") (pinfunction "2_2") (pintype "passive"))
      (node (ref "U8") (pin "7") (pinfunction "HB_7") (pintype "passive"))
    )
    (net (code "36") (name "Net-(U8-RT)") (class "Default")
      (node (ref "R15") (pin "1") (pinfunction "1_1") (pintype "passive"))
      (node (ref "U8") (pin "15") (pinfunction "RT_15") (pintype "passive"))
    )
    (net (code "37") (name "Net-(U8-SS)") (class "Default")
      (node (ref "C25") (pin "1") (pinfunction "1_1") (pintype "passive"))
      (node (ref "U8") (pin "17") (pinfunction "SS_17") (pintype "passive"))
    )
    (net (code "38") (name "Net-(U8-TRK)") (class "Default")
      (node (ref "C30") (pin "1") (pinfunction "1_1") (pintype "passive"))
      (node (ref "R16") (pin "2") (pinfunction "2_2") (pintype "passive"))
      (node (ref "R18") (pin "1") (pinfunction "1_1") (pintype "passive"))
      (node (ref "U8") (pin "18") (pinfunction "TRK_18") (pintype "passive"))
    )
    (net (code "39") (name "Net-(U8-UVLO_EN)") (class "Default")
      (node (ref "R13") (pin "2") (pinfunction "2_2") (pintype "passive"))
      (node (ref "R14") (pin "1") (pinfunction "1_1") (pintype "passive"))
      (node (ref "U8") (pin "13") (pinfunction "UVLO_EN_13") (pintype "input"))
    )
    (net (code "40") (name "Net-(U8-VCC)") (class "Default")
      (node (ref "C27") (pin "1") (pinfunction "1_1") (pintype "passive"))
      (node (ref "U8") (pin "9") (pinfunction "VCC_9") (pintype "passive"))
    )
    (net (code "41") (name "Net-(U8-VREF_RANGE)") (class "Default")
      (node (ref "C28") (pin "1") (pinfunction "1_1") (pintype "passive"))
      (node (ref "R17") (pin "1") (pinfunction "1_1") (pintype "passive"))
      (node (ref "U8") (pin "16") (pinfunction "VREF_RANGE_16") (pintype "passive"))
    )
    (net (code "42") (name "unconnected-(U1-CMPM-Pad2)") (class "Default")
      (node (ref "U1") (pin "2") (pinfunction "CMPM_2") (pintype "passive"))
    )
    (net (code "43") (name "unconnected-(U1-CMPOUT-Pad1)") (class "Default")
      (node (ref "U1") (pin "1") (pinfunction "CMPOUT_1") (pintype "passive"))
    )
    (net (code "44") (name "unconnected-(U1-CMPP-Pad3)") (class "Default")
      (node (ref "U1") (pin "3") (pinfunction "CMPP_3") (pintype "passive"))
    )
    (net (code "45") (name "unconnected-(U1-FLT_N-Pad20)") (class "Default")
      (node (ref "U1") (pin "20") (pinfunction "FLT_N_20") (pintype "output"))
    )
    (net (code "46") (name "unconnected-(U1-MODE-Pad17)") (class "Default")
      (node (ref "U1") (pin "17") (pinfunction "MODE_17") (pintype "input"))
    )
    (net (code "47") (name "unconnected-(U1-NC-Pad15)") (class "Default")
      (node (ref "U1") (pin "15") (pinfunction "NC_15") (pintype "passive"))
    )
    (net (code "48") (name "unconnected-(U1-NC-Pad16)") (class "Default")
      (node (ref "U1") (pin "16") (pinfunction "NC_16") (pintype "passive"))
    )
    (net (code "49") (name "unconnected-(U1-PG-Pad19)") (class "Default")
      (node (ref "U1") (pin "19") (pinfunction "PG_19") (pintype "open_collector"))
    )
    (net (code "50") (name "unconnected-(U3-NC-Pad3)") (class "Default")
      (node (ref "U3") (pin "3") (pinfunction "NC_3") (pintype "passive"))
    )
    (net (code "51") (name "unconnected-(U3-NC-Pad5)") (class "Default")
      (node (ref "U3") (pin "5") (pinfunction "NC_5") (pintype "passive"))
    )
    (net (code "52") (name "unconnected-(U6-EN-Pad5)") (class "Default")
      (node (ref "U6") (pin "5") (pinfunction "EN_5") (pintype "input"))
    )
    (net (code "53") (name "unconnected-(U6-NC-Pad2)") (class "Default")
      (node (ref "U6") (pin "2") (pinfunction "NC_2") (pintype "passive"))
    )
    (net (code "54") (name "unconnected-(U6-NC-Pad7)") (class "Default")
      (node (ref "U6") (pin "7") (pinfunction "NC_7") (pintype "passive"))
    )
    (net (code "55") (name "unconnected-(U8-MODE-Pad12)") (class "Default")
      (node (ref "U8") (pin "12") (pinfunction "MODE_12") (pintype "passive"))
    )
  )
)
